# BasePCB.net
KiCad netlist of a schematic drawn in EAGLE
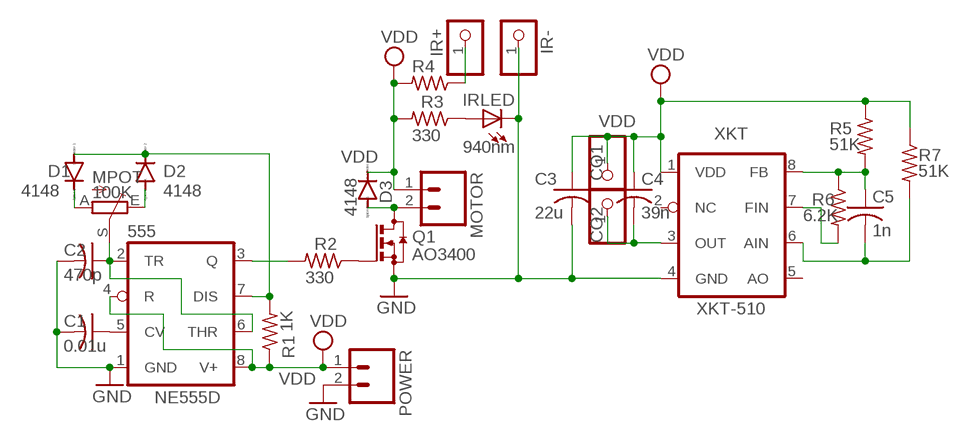
[diagram p0: schematic, sheet 1]

(export (version "E")
  (design (tool "Eeschema 10.0.6"))
  (components
    (comp (ref "555")
      (value "NE555D")
      (footprint "eagle-import:SO08")
      (libsource (lib "eagle-import") (part "555DNE"))
    )
    (comp (ref "C1")
      (value "0.01u")
      (footprint "eagle-import:C0603K")
      (libsource (lib "eagle-import") (part "C-USC0603K"))
    )
    (comp (ref "C2")
      (value "470p")
      (footprint "eagle-import:C0603K")
      (libsource (lib "eagle-import") (part "C-USC0603K"))
    )
    (comp (ref "C3")
      (value "22u")
      (footprint "eagle-import:C0805K")
      (libsource (lib "eagle-import") (part "C-USC0805K"))
    )
    (comp (ref "C4")
      (value "39n")
      (footprint "eagle-import:C0805K")
      (libsource (lib "eagle-import") (part "C-USC0805K"))
    )
    (comp (ref "C5")
      (value "1n")
      (footprint "eagle-import:C0805K")
      (libsource (lib "eagle-import") (part "C-USC0805K"))
    )
    (comp (ref "CO1")
      (value "PINHD-1X1CB")
      (footprint "eagle-import:1X01-CLEANBIG")
      (libsource (lib "eagle-import") (part "PINHD-1X1CB"))
    )
    (comp (ref "CO2")
      (value "PINHD-1X1CB")
      (footprint "eagle-import:1X01-CLEANBIG")
      (libsource (lib "eagle-import") (part "PINHD-1X1CB"))
    )
    (comp (ref "D1")
      (value "4148")
      (footprint "eagle-import:MINIMELF")
      (libsource (lib "eagle-import") (part "DIODE-MINIMELF"))
    )
    (comp (ref "D2")
      (value "4148")
      (footprint "eagle-import:MINIMELF")
      (libsource (lib "eagle-import") (part "DIODE-MINIMELF"))
    )
    (comp (ref "D3")
      (value "4148")
      (footprint "eagle-import:MINIMELF")
      (libsource (lib "eagle-import") (part "DIODE-MINIMELF"))
    )
    (comp (ref "IR+")
      (value "PINHD-1X1CB")
      (footprint "eagle-import:1X01-CLEANBIG")
      (libsource (lib "eagle-import") (part "PINHD-1X1CB"))
    )
    (comp (ref "IR-")
      (value "PINHD-1X1CB")
      (footprint "eagle-import:1X01-CLEANBIG")
      (libsource (lib "eagle-import") (part "PINHD-1X1CB"))
    )
    (comp (ref "IRLED")
      (value "940nm")
      (footprint "eagle-import:CHIPLED_0603")
      (libsource (lib "eagle-import") (part "LEDCHIPLED_0603"))
    )
    (comp (ref "MOTOR")
      (value "M021X02_NO_SILK")
      (footprint "eagle-import:1X02_NO_SILK")
      (libsource (lib "eagle-import") (part "M021X02_NO_SILK"))
    )
    (comp (ref "MPOT")
      (value "100K")
      (footprint "eagle-import:CA6V")
      (libsource (lib "eagle-import") (part "TRIM_EU-CA6V"))
    )
    (comp (ref "POWER")
      (value "M021X02_NO_SILK")
      (footprint "eagle-import:1X02_NO_SILK")
      (libsource (lib "eagle-import") (part "M021X02_NO_SILK"))
    )
    (comp (ref "Q1")
      (value "AO3400")
      (footprint "eagle-import:SOT23")
      (libsource (lib "eagle-import") (part "BSS123"))
    )
    (comp (ref "R1")
      (value "1K")
      (footprint "eagle-import:R0603")
      (libsource (lib "eagle-import") (part "R-US_R0603"))
    )
    (comp (ref "R2")
      (value "330")
      (footprint "eagle-import:R0603")
      (libsource (lib "eagle-import") (part "R-US_R0603"))
    )
    (comp (ref "R3")
      (value "330")
      (footprint "eagle-import:R0603")
      (libsource (lib "eagle-import") (part "R-US_R0603"))
    )
    (comp (ref "R4")
      (value "330")
      (footprint "eagle-import:R0603")
      (libsource (lib "eagle-import") (part "R-US_R0603"))
    )
    (comp (ref "R5")
      (value "51K")
      (footprint "eagle-import:R0603")
      (libsource (lib "eagle-import") (part "R-US_R0603"))
    )
    (comp (ref "R6")
      (value "6.2K")
      (footprint "eagle-import:R0603")
      (libsource (lib "eagle-import") (part "R-US_R0603"))
    )
    (comp (ref "R7")
      (value "51K")
      (footprint "eagle-import:R0603")
      (libsource (lib "eagle-import") (part "R-US_R0603"))
    )
    (comp (ref "XKT")
      (value "XKT-510")
      (footprint "eagle-import:SO08")
      (libsource (lib "eagle-import") (part "XKT-510"))
    )
  )
  (nets
    (net (code "1") (name "GND") (class "Default")
      (node (ref "555") (pin "1") (pinfunction "GND_1") (pintype "power_in"))
      (node (ref "C1") (pin "2") (pinfunction "2_2") (pintype "passive"))
      (node (ref "C2") (pin "2") (pinfunction "2_2") (pintype "passive"))
      (node (ref "C3") (pin "2") (pinfunction "2_2") (pintype "passive"))
      (node (ref "IR-") (pin "1") (pinfunction "1_1") (pintype "passive"))
      (node (ref "IRLED") (pin "C") (pinfunction "C_C") (pintype "passive"))
      (node (ref "POWER") (pin "2") (pinfunction "2_2") (pintype "passive"))
      (node (ref "Q1") (pin "2") (pinfunction "S_2") (pintype "passive"))
      (node (ref "XKT") (pin "4") (pinfunction "GND_4") (pintype "power_in"))
    )
    (net (code "2") (name "Net-(555-CV)") (class "Default")
      (node (ref "555") (pin "5") (pinfunction "CV_5") (pintype "input"))
      (node (ref "C1") (pin "1") (pinfunction "1_1") (pintype "passive"))
    )
    (net (code "3") (name "Net-(555-DIS)") (class "Default")
      (node (ref "555") (pin "7") (pinfunction "DIS_7") (pintype "input"))
      (node (ref "D1") (pin "A") (pinfunction "A_A") (pintype "passive"))
      (node (ref "D2") (pin "C") (pinfunction "C_C") (pintype "passive"))
      (node (ref "R1") (pin "2") (pinfunction "2_2") (pintype "passive"))
    )
    (net (code "4") (name "Net-(555-Q)") (class "Default")
      (node (ref "555") (pin "3") (pinfunction "Q_3") (pintype "output"))
      (node (ref "R2") (pin "2") (pinfunction "2_2") (pintype "passive"))
    )
    (net (code "5") (name "Net-(555-THR)") (class "Default")
      (node (ref "555") (pin "2") (pinfunction "TR_2") (pintype "input"))
      (node (ref "555") (pin "6") (pinfunction "THR_6") (pintype "input"))
      (node (ref "C2") (pin "1") (pinfunction "1_1") (pintype "passive"))
      (node (ref "MPOT") (pin "S") (pinfunction "S_S") (pintype "passive"))
    )
    (net (code "6") (name "Net-(D1-PadC)") (class "Default")
      (node (ref "D1") (pin "C") (pinfunction "C_C") (pintype "passive"))
      (node (ref "MPOT") (pin "A") (pinfunction "A_A") (pintype "passive"))
    )
    (net (code "7") (name "Net-(D2-PadA)") (class "Default")
      (node (ref "D2") (pin "A") (pinfunction "A_A") (pintype "passive"))
      (node (ref "MPOT") (pin "E") (pinfunction "E_E") (pintype "passive"))
    )
    (net (code "8") (name "Net-(IR+-Pad1)") (class "Default")
      (node (ref "IR+") (pin "1") (pinfunction "1_1") (pintype "passive"))
      (node (ref "R4") (pin "1") (pinfunction "1_1") (pintype "passive"))
    )
    (net (code "9") (name "Net-(IRLED-PadA)") (class "Default")
      (node (ref "IRLED") (pin "A") (pinfunction "A_A") (pintype "passive"))
      (node (ref "R3") (pin "1") (pinfunction "1_1") (pintype "passive"))
    )
    (net (code "10") (name "Net-(Q1-D)") (class "Default")
      (node (ref "D3") (pin "A") (pinfunction "A_A") (pintype "passive"))
      (node (ref "MOTOR") (pin "2") (pinfunction "2_2") (pintype "passive"))
      (node (ref "Q1") (pin "3") (pinfunction "D_3") (pintype "passive"))
    )
    (net (code "11") (name "Net-(Q1-G)") (class "Default")
      (node (ref "Q1") (pin "1") (pinfunction "G_1") (pintype "passive"))
      (node (ref "R2") (pin "1") (pinfunction "1_1") (pintype "passive"))
    )
    (net (code "12") (name "Net-(XKT-AIN)") (class "Default")
      (node (ref "C5") (pin "2") (pinfunction "2_2") (pintype "passive"))
      (node (ref "R7") (pin "2") (pinfunction "2_2") (pintype "passive"))
      (node (ref "XKT") (pin "6") (pinfunction "AIN_6") (pintype "bidirectional"))
    )
    (net (code "13") (name "Net-(XKT-FB)") (class "Default")
      (node (ref "C5") (pin "1") (pinfunction "1_1") (pintype "passive"))
      (node (ref "R5") (pin "2") (pinfunction "2_2") (pintype "passive"))
      (node (ref "R6") (pin "1") (pinfunction "1_1") (pintype "passive"))
      (node (ref "XKT") (pin "8") (pinfunction "FB_8") (pintype "bidirectional"))
    )
    (net (code "14") (name "Net-(XKT-FIN)") (class "Default")
      (node (ref "R6") (pin "2") (pinfunction "2_2") (pintype "passive"))
      (node (ref "XKT") (pin "7") (pinfunction "FIN_7") (pintype "bidirectional"))
    )
    (net (code "15") (name "Net-(XKT-OUT)") (class "Default")
      (node (ref "C4") (pin "2") (pinfunction "2_2") (pintype "passive"))
      (node (ref "CO2") (pin "1") (pinfunction "1_1") (pintype "passive"))
      (node (ref "XKT") (pin "3") (pinfunction "OUT_3") (pintype "bidirectional"))
    )
    (net (code "16") (name "VDD") (class "Default")
      (node (ref "555") (pin "4") (pinfunction "R_4") (pintype "input"))
      (node (ref "555") (pin "8") (pinfunction "V+_8") (pintype "power_in"))
      (node (ref "C3") (pin "1") (pinfunction "1_1") (pintype "passive"))
      (node (ref "C4") (pin "1") (pinfunction "1_1") (pintype "passive"))
      (node (ref "CO1") (pin "1") (pinfunction "1_1") (pintype "passive"))
      (node (ref "D3") (pin "C") (pinfunction "C_C") (pintype "passive"))
      (node (ref "MOTOR") (pin "1") (pinfunction "1_1") (pintype "passive"))
      (node (ref "POWER") (pin "1") (pinfunction "1_1") (pintype "passive"))
      (node (ref "R1") (pin "1") (pinfunction "1_1") (pintype "passive"))
      (node (ref "R3") (pin "2") (pinfunction "2_2") (pintype "passive"))
      (node (ref "R4") (pin "2") (pinfunction "2_2") (pintype "passive"))
      (node (ref "R5") (pin "1") (pinfunction "1_1") (pintype "passive"))
      (node (ref "R7") (pin "1") (pinfunction "1_1") (pintype "passive"))
      (node (ref "XKT") (pin "1") (pinfunction "VDD_1") (pintype "power_in"))
    )
    (net (code "17") (name "unconnected-(XKT-AO-Pad5)") (class "Default")
      (node (ref "XKT") (pin "5") (pinfunction "AO_5") (pintype "bidirectional"))
    )
    (net (code "18") (name "unconnected-(XKT-NC-Pad2)") (class "Default")
      (node (ref "XKT") (pin "2") (pinfunction "NC_2") (pintype "bidirectional"))
    )
  )
)
